# USBasp.net
KiCad netlist of a schematic drawn in EAGLE
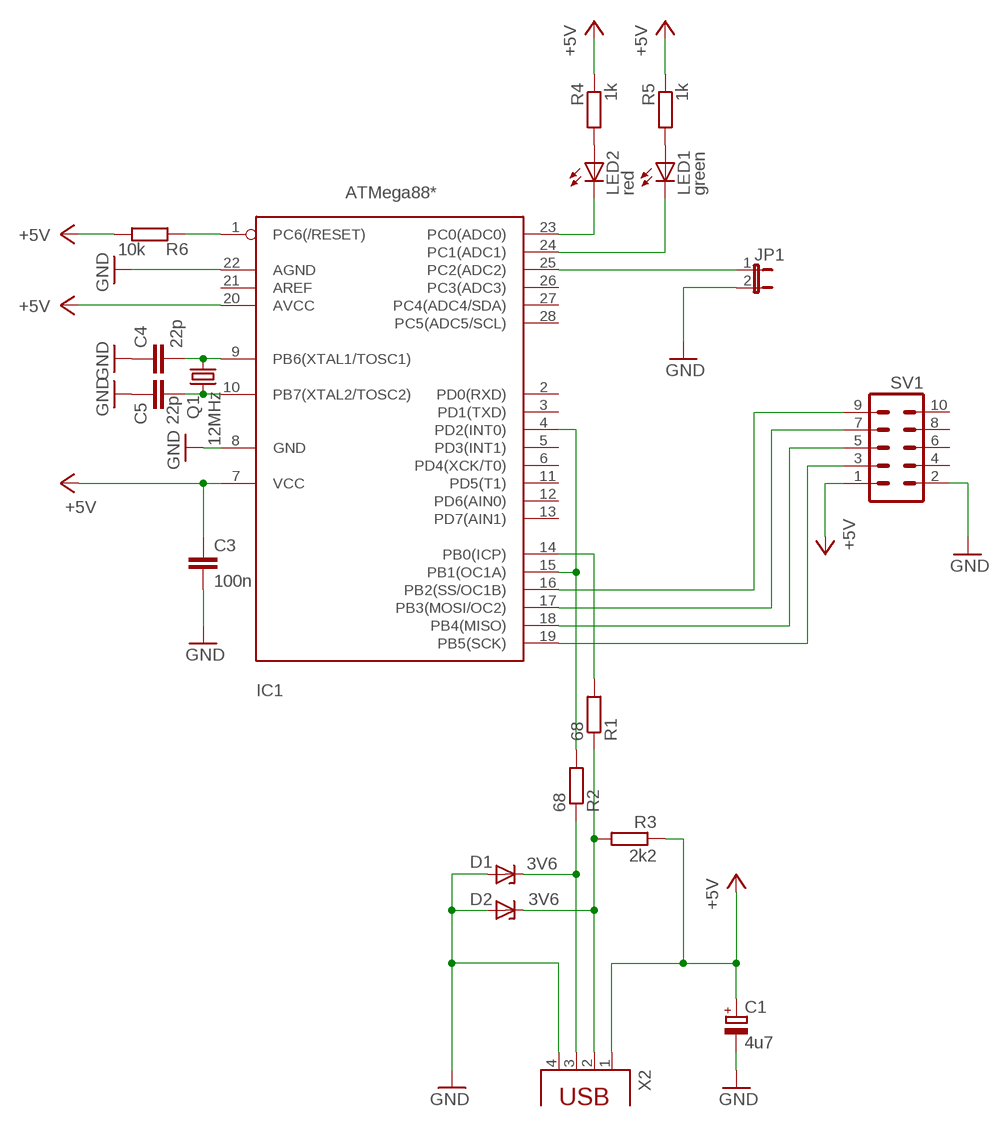
[diagram p0: schematic, sheet 1]

(export (version "E")
  (design (tool "Eeschema 10.0.6"))
  (components
    (comp (ref "C1")
      (value "4u7")
      (footprint "eagle-import:E2,5-5")
      (libsource (lib "eagle-import") (part "CPOL-EUE2.5-5"))
    )
    (comp (ref "C3")
      (value "100n")
      (footprint "eagle-import:C025-024X044")
      (libsource (lib "eagle-import") (part "C-EU025-024X044"))
    )
    (comp (ref "C4")
      (value "22p")
      (footprint "eagle-import:C025-024X044")
      (libsource (lib "eagle-import") (part "C-EU025-024X044"))
    )
    (comp (ref "C5")
      (value "22p")
      (footprint "eagle-import:C025-024X044")
      (libsource (lib "eagle-import") (part "C-EU025-024X044"))
    )
    (comp (ref "D1")
      (value "3V6")
      (footprint "eagle-import:DO34Z7")
      (libsource (lib "eagle-import") (part "ZENER-DIODEDO34-7"))
    )
    (comp (ref "D2")
      (value "3V6")
      (footprint "eagle-import:DO34Z7")
      (libsource (lib "eagle-import") (part "ZENER-DIODEDO34-7"))
    )
    (comp (ref "IC1")
      (value "ATMega88*")
      (footprint "eagle-import:DIL28-3")
      (libsource (lib "eagle-import") (part "MEGA8-P"))
    )
    (comp (ref "JP1")
      (value "JP1E")
      (footprint "eagle-import:JP1")
      (libsource (lib "eagle-import") (part "JP1E"))
    )
    (comp (ref "LED1")
      (value "green")
      (footprint "eagle-import:LED3MM")
      (libsource (lib "eagle-import") (part "LED3MM"))
    )
    (comp (ref "LED2")
      (value "red")
      (footprint "eagle-import:LED3MM")
      (libsource (lib "eagle-import") (part "LED3MM"))
    )
    (comp (ref "Q1")
      (value "12MHz")
      (footprint "eagle-import:HC49_S")
      (libsource (lib "eagle-import") (part "CRYTALHC49S"))
    )
    (comp (ref "R1")
      (value "68")
      (footprint "eagle-import:0207_10")
      (libsource (lib "eagle-import") (part "R-EU_0207/10"))
    )
    (comp (ref "R2")
      (value "68")
      (footprint "eagle-import:0207_10")
      (libsource (lib "eagle-import") (part "R-EU_0207/10"))
    )
    (comp (ref "R3")
      (value "2k2")
      (footprint "eagle-import:0207_10")
      (libsource (lib "eagle-import") (part "R-EU_0207/10"))
    )
    (comp (ref "R4")
      (value "1k")
      (footprint "eagle-import:0207_10")
      (libsource (lib "eagle-import") (part "R-EU_0207/10"))
    )
    (comp (ref "R5")
      (value "1k")
      (footprint "eagle-import:0207_10")
      (libsource (lib "eagle-import") (part "R-EU_0207/10"))
    )
    (comp (ref "R6")
      (value "10k")
      (footprint "eagle-import:0207_10")
      (libsource (lib "eagle-import") (part "R-EU_0207/10"))
    )
    (comp (ref "SV1")
      (value "MA05-2")
      (footprint "eagle-import:MA05-2")
      (libsource (lib "eagle-import") (part "MA05-2"))
    )
    (comp (ref "X2")
      (value "PN87520")
      (footprint "eagle-import:PN87520")
      (libsource (lib "eagle-import") (part "PN87520"))
    )
  )
  (nets
    (net (code "1") (name "+5V") (class "Default")
      (node (ref "C1") (pin "+") (pinfunction "+_+") (pintype "passive"))
      (node (ref "C3") (pin "1") (pinfunction "1_1") (pintype "passive"))
      (node (ref "IC1") (pin "20") (pinfunction "AVCC_20") (pintype "bidirectional"))
      (node (ref "IC1") (pin "7") (pinfunction "VCC_7") (pintype "bidirectional"))
      (node (ref "R3") (pin "1") (pinfunction "1_1") (pintype "passive"))
      (node (ref "R4") (pin "1") (pinfunction "1_1") (pintype "passive"))
      (node (ref "R5") (pin "1") (pinfunction "1_1") (pintype "passive"))
      (node (ref "R6") (pin "1") (pinfunction "1_1") (pintype "passive"))
      (node (ref "SV1") (pin "1") (pinfunction "1_1") (pintype "passive"))
      (node (ref "X2") (pin "1") (pinfunction "1_1") (pintype "passive"))
    )
    (net (code "2") (name "GND") (class "Default")
      (node (ref "C1") (pin "-") (pinfunction "-_-") (pintype "passive"))
      (node (ref "C3") (pin "2") (pinfunction "2_2") (pintype "passive"))
      (node (ref "C4") (pin "1") (pinfunction "1_1") (pintype "passive"))
      (node (ref "C5") (pin "1") (pinfunction "1_1") (pintype "passive"))
      (node (ref "D1") (pin "A") (pinfunction "A_A") (pintype "passive"))
      (node (ref "D2") (pin "A") (pinfunction "A_A") (pintype "passive"))
      (node (ref "IC1") (pin "22") (pinfunction "AGND_22") (pintype "bidirectional"))
      (node (ref "IC1") (pin "8") (pinfunction "GND_8") (pintype "bidirectional"))
      (node (ref "JP1") (pin "2") (pinfunction "2_2") (pintype "passive"))
      (node (ref "SV1") (pin "2") (pinfunction "2_2") (pintype "passive"))
      (node (ref "X2") (pin "4") (pinfunction "4_4") (pintype "passive"))
    )
    (net (code "3") (name "Net-(D1-PadC)") (class "Default")
      (node (ref "D1") (pin "C") (pinfunction "C_C") (pintype "passive"))
      (node (ref "R2") (pin "1") (pinfunction "1_1") (pintype "passive"))
      (node (ref "X2") (pin "3") (pinfunction "3_3") (pintype "passive"))
    )
    (net (code "4") (name "Net-(D2-PadC)") (class "Default")
      (node (ref "D2") (pin "C") (pinfunction "C_C") (pintype "passive"))
      (node (ref "R1") (pin "1") (pinfunction "1_1") (pintype "passive"))
      (node (ref "R3") (pin "2") (pinfunction "2_2") (pintype "passive"))
      (node (ref "X2") (pin "2") (pinfunction "2_2") (pintype "passive"))
    )
    (net (code "5") (name "Net-(IC1-PB0(ICP))") (class "Default")
      (node (ref "IC1") (pin "14") (pinfunction "PB0(ICP)_14") (pintype "bidirectional"))
      (node (ref "R1") (pin "2") (pinfunction "2_2") (pintype "passive"))
    )
    (net (code "6") (name "Net-(IC1-PB1(OC1A))") (class "Default")
      (node (ref "IC1") (pin "15") (pinfunction "PB1(OC1A)_15") (pintype "bidirectional"))
      (node (ref "IC1") (pin "4") (pinfunction "PD2(INT0)_4") (pintype "bidirectional"))
      (node (ref "R2") (pin "2") (pinfunction "2_2") (pintype "passive"))
    )
    (net (code "7") (name "Net-(IC1-PB2(SS{slash}OC1B))") (class "Default")
      (node (ref "IC1") (pin "16") (pinfunction "PB2(SS/OC1B)_16") (pintype "bidirectional"))
      (node (ref "SV1") (pin "9") (pinfunction "9_9") (pintype "passive"))
    )
    (net (code "8") (name "Net-(IC1-PB3(MOSI{slash}OC2))") (class "Default")
      (node (ref "IC1") (pin "17") (pinfunction "PB3(MOSI/OC2)_17") (pintype "bidirectional"))
      (node (ref "SV1") (pin "7") (pinfunction "7_7") (pintype "passive"))
    )
    (net (code "9") (name "Net-(IC1-PB4(MISO))") (class "Default")
      (node (ref "IC1") (pin "18") (pinfunction "PB4(MISO)_18") (pintype "bidirectional"))
      (node (ref "SV1") (pin "5") (pinfunction "5_5") (pintype "passive"))
    )
    (net (code "10") (name "Net-(IC1-PB5(SCK))") (class "Default")
      (node (ref "IC1") (pin "19") (pinfunction "PB5(SCK)_19") (pintype "bidirectional"))
      (node (ref "SV1") (pin "3") (pinfunction "3_3") (pintype "passive"))
    )
    (net (code "11") (name "Net-(IC1-PB6(XTAL1{slash}TOSC1))") (class "Default")
      (node (ref "C4") (pin "2") (pinfunction "2_2") (pintype "passive"))
      (node (ref "IC1") (pin "9") (pinfunction "PB6(XTAL1/TOSC1)_9") (pintype "bidirectional"))
      (node (ref "Q1") (pin "2") (pinfunction "2_2") (pintype "passive"))
    )
    (net (code "12") (name "Net-(IC1-PB7(XTAL2{slash}TOSC2))") (class "Default")
      (node (ref "C5") (pin "2") (pinfunction "2_2") (pintype "passive"))
      (node (ref "IC1") (pin "10") (pinfunction "PB7(XTAL2/TOSC2)_10") (pintype "bidirectional"))
      (node (ref "Q1") (pin "1") (pinfunction "1_1") (pintype "passive"))
    )
    (net (code "13") (name "Net-(IC1-PC0(ADC0))") (class "Default")
      (node (ref "IC1") (pin "23") (pinfunction "PC0(ADC0)_23") (pintype "bidirectional"))
      (node (ref "LED2") (pin "K") (pinfunction "C_K") (pintype "passive"))
    )
    (net (code "14") (name "Net-(IC1-PC1(ADC1))") (class "Default")
      (node (ref "IC1") (pin "24") (pinfunction "PC1(ADC1)_24") (pintype "bidirectional"))
      (node (ref "LED1") (pin "K") (pinfunction "C_K") (pintype "passive"))
    )
    (net (code "15") (name "Net-(IC1-PC2(ADC2))") (class "Default")
      (node (ref "IC1") (pin "25") (pinfunction "PC2(ADC2)_25") (pintype "bidirectional"))
      (node (ref "JP1") (pin "1") (pinfunction "1_1") (pintype "passive"))
    )
    (net (code "16") (name "Net-(IC1-PC6({slash}RESET))") (class "Default")
      (node (ref "IC1") (pin "1") (pinfunction "PC6(/RESET)_1") (pintype "bidirectional"))
      (node (ref "R6") (pin "2") (pinfunction "2_2") (pintype "passive"))
    )
    (net (code "17") (name "Net-(LED1-PadA)") (class "Default")
      (node (ref "LED1") (pin "A") (pinfunction "A_A") (pintype "passive"))
      (node (ref "R5") (pin "2") (pinfunction "2_2") (pintype "passive"))
    )
    (net (code "18") (name "Net-(LED2-PadA)") (class "Default")
      (node (ref "LED2") (pin "A") (pinfunction "A_A") (pintype "passive"))
      (node (ref "R4") (pin "2") (pinfunction "2_2") (pintype "passive"))
    )
    (net (code "19") (name "unconnected-(IC1-AREF-Pad21)") (class "Default")
      (node (ref "IC1") (pin "21") (pinfunction "AREF_21") (pintype "bidirectional"))
    )
    (net (code "20") (name "unconnected-(IC1-PC3(ADC3)-Pad26)") (class "Default")
      (node (ref "IC1") (pin "26") (pinfunction "PC3(ADC3)_26") (pintype "bidirectional"))
    )
    (net (code "21") (name "unconnected-(IC1-PC4(ADC4{slash}SDA)-Pad27)") (class "Default")
      (node (ref "IC1") (pin "27") (pinfunction "PC4(ADC4/SDA)_27") (pintype "bidirectional"))
    )
    (net (code "22") (name "unconnected-(IC1-PC5(ADC5{slash}SCL)-Pad28)") (class "Default")
      (node (ref "IC1") (pin "28") (pinfunction "PC5(ADC5/SCL)_28") (pintype "bidirectional"))
    )
    (net (code "23") (name "unconnected-(IC1-PD0(RXD)-Pad2)") (class "Default")
      (node (ref "IC1") (pin "2") (pinfunction "PD0(RXD)_2") (pintype "bidirectional"))
    )
    (net (code "24") (name "unconnected-(IC1-PD1(TXD)-Pad3)") (class "Default")
      (node (ref "IC1") (pin "3") (pinfunction "PD1(TXD)_3") (pintype "bidirectional"))
    )
    (net (code "25") (name "unconnected-(IC1-PD3(INT1)-Pad5)") (class "Default")
      (node (ref "IC1") (pin "5") (pinfunction "PD3(INT1)_5") (pintype "bidirectional"))
    )
    (net (code "26") (name "unconnected-(IC1-PD4(XCK{slash}T0)-Pad6)") (class "Default")
      (node (ref "IC1") (pin "6") (pinfunction "PD4(XCK/T0)_6") (pintype "bidirectional"))
    )
    (net (code "27") (name "unconnected-(IC1-PD5(T1)-Pad11)") (class "Default")
      (node (ref "IC1") (pin "11") (pinfunction "PD5(T1)_11") (pintype "bidirectional"))
    )
    (net (code "28") (name "unconnected-(IC1-PD6(AIN0)-Pad12)") (class "Default")
      (node (ref "IC1") (pin "12") (pinfunction "PD6(AIN0)_12") (pintype "bidirectional"))
    )
    (net (code "29") (name "unconnected-(IC1-PD7(AIN1)-Pad13)") (class "Default")
      (node (ref "IC1") (pin "13") (pinfunction "PD7(AIN1)_13") (pintype "bidirectional"))
    )
    (net (code "30") (name "unconnected-(SV1-Pad4)") (class "Default")
      (node (ref "SV1") (pin "4") (pinfunction "4_4") (pintype "passive"))
    )
    (net (code "31") (name "unconnected-(SV1-Pad6)") (class "Default")
      (node (ref "SV1") (pin "6") (pinfunction "6_6") (pintype "passive"))
    )
    (net (code "32") (name "unconnected-(SV1-Pad8)") (class "Default")
      (node (ref "SV1") (pin "8") (pinfunction "8_8") (pintype "passive"))
    )
    (net (code "33") (name "unconnected-(SV1-Pad10)") (class "Default")
      (node (ref "SV1") (pin "10") (pinfunction "10_10") (pintype "passive"))
    )
  )
)
